# CROSSnew.net
KiCad netlist of a schematic drawn in EAGLE
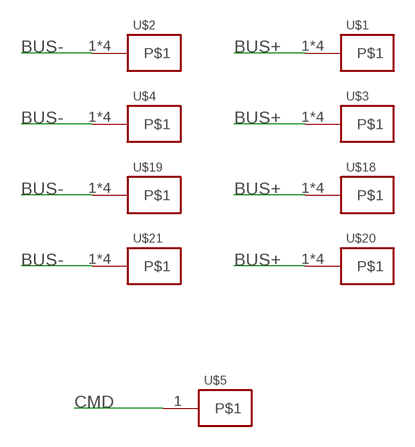
[diagram p0: schematic, sheet 1]

(export (version "E")
  (design (tool "Eeschema 10.0.6"))
  (components
    (comp (ref "U$1")
      (value "KCONNECT-")
      (footprint "eagle-import:KCONNECT-")
      (libsource (lib "eagle-import") (part "KCONNECT-"))
    )
    (comp (ref "U$2")
      (value "KCONNECT-")
      (footprint "eagle-import:KCONNECT-")
      (libsource (lib "eagle-import") (part "KCONNECT-"))
    )
    (comp (ref "U$3")
      (value "KCONNECT-")
      (footprint "eagle-import:KCONNECT-")
      (libsource (lib "eagle-import") (part "KCONNECT-"))
    )
    (comp (ref "U$4")
      (value "KCONNECT-")
      (footprint "eagle-import:KCONNECT-")
      (libsource (lib "eagle-import") (part "KCONNECT-"))
    )
    (comp (ref "U$5")
      (value "KCONNECTQUAD-")
      (footprint "eagle-import:KCONNECT-_QUAD")
      (libsource (lib "eagle-import") (part "KCONNECTQUAD-"))
    )
    (comp (ref "U$18")
      (value "KCONNECT-")
      (footprint "eagle-import:KCONNECT-")
      (libsource (lib "eagle-import") (part "KCONNECT-"))
    )
    (comp (ref "U$19")
      (value "KCONNECT-")
      (footprint "eagle-import:KCONNECT-")
      (libsource (lib "eagle-import") (part "KCONNECT-"))
    )
    (comp (ref "U$20")
      (value "KCONNECT-")
      (footprint "eagle-import:KCONNECT-")
      (libsource (lib "eagle-import") (part "KCONNECT-"))
    )
    (comp (ref "U$21")
      (value "KCONNECT-")
      (footprint "eagle-import:KCONNECT-")
      (libsource (lib "eagle-import") (part "KCONNECT-"))
    )
  )
  (nets
    (net (code "1") (name "/BUS+") (class "Default")
      (node (ref "U$1") (pin "1") (pinfunction "P$1_1") (pintype "bidirectional"))
      (node (ref "U$1") (pin "2") (pinfunction "P$1_2") (pintype "bidirectional"))
      (node (ref "U$1") (pin "3") (pinfunction "P$1_3") (pintype "bidirectional"))
      (node (ref "U$1") (pin "4") (pinfunction "P$1_4") (pintype "bidirectional"))
      (node (ref "U$18") (pin "1") (pinfunction "P$1_1") (pintype "bidirectional"))
      (node (ref "U$18") (pin "2") (pinfunction "P$1_2") (pintype "bidirectional"))
      (node (ref "U$18") (pin "3") (pinfunction "P$1_3") (pintype "bidirectional"))
      (node (ref "U$18") (pin "4") (pinfunction "P$1_4") (pintype "bidirectional"))
      (node (ref "U$20") (pin "1") (pinfunction "P$1_1") (pintype "bidirectional"))
      (node (ref "U$20") (pin "2") (pinfunction "P$1_2") (pintype "bidirectional"))
      (node (ref "U$20") (pin "3") (pinfunction "P$1_3") (pintype "bidirectional"))
      (node (ref "U$20") (pin "4") (pinfunction "P$1_4") (pintype "bidirectional"))
      (node (ref "U$3") (pin "1") (pinfunction "P$1_1") (pintype "bidirectional"))
      (node (ref "U$3") (pin "2") (pinfunction "P$1_2") (pintype "bidirectional"))
      (node (ref "U$3") (pin "3") (pinfunction "P$1_3") (pintype "bidirectional"))
      (node (ref "U$3") (pin "4") (pinfunction "P$1_4") (pintype "bidirectional"))
    )
    (net (code "2") (name "/BUS-") (class "Default")
      (node (ref "U$19") (pin "1") (pinfunction "P$1_1") (pintype "bidirectional"))
      (node (ref "U$19") (pin "2") (pinfunction "P$1_2") (pintype "bidirectional"))
      (node (ref "U$19") (pin "3") (pinfunction "P$1_3") (pintype "bidirectional"))
      (node (ref "U$19") (pin "4") (pinfunction "P$1_4") (pintype "bidirectional"))
      (node (ref "U$2") (pin "1") (pinfunction "P$1_1") (pintype "bidirectional"))
      (node (ref "U$2") (pin "2") (pinfunction "P$1_2") (pintype "bidirectional"))
      (node (ref "U$2") (pin "3") (pinfunction "P$1_3") (pintype "bidirectional"))
      (node (ref "U$2") (pin "4") (pinfunction "P$1_4") (pintype "bidirectional"))
      (node (ref "U$21") (pin "1") (pinfunction "P$1_1") (pintype "bidirectional"))
      (node (ref "U$21") (pin "2") (pinfunction "P$1_2") (pintype "bidirectional"))
      (node (ref "U$21") (pin "3") (pinfunction "P$1_3") (pintype "bidirectional"))
      (node (ref "U$21") (pin "4") (pinfunction "P$1_4") (pintype "bidirectional"))
      (node (ref "U$4") (pin "1") (pinfunction "P$1_1") (pintype "bidirectional"))
      (node (ref "U$4") (pin "2") (pinfunction "P$1_2") (pintype "bidirectional"))
      (node (ref "U$4") (pin "3") (pinfunction "P$1_3") (pintype "bidirectional"))
      (node (ref "U$4") (pin "4") (pinfunction "P$1_4") (pintype "bidirectional"))
    )
    (net (code "3") (name "/CMD") (class "Default")
      (node (ref "U$5") (pin "1") (pinfunction "P$1_1") (pintype "bidirectional"))
    )
  )
)
